# Adafruit_QT_Py.net
KiCad netlist of a schematic drawn in EAGLE
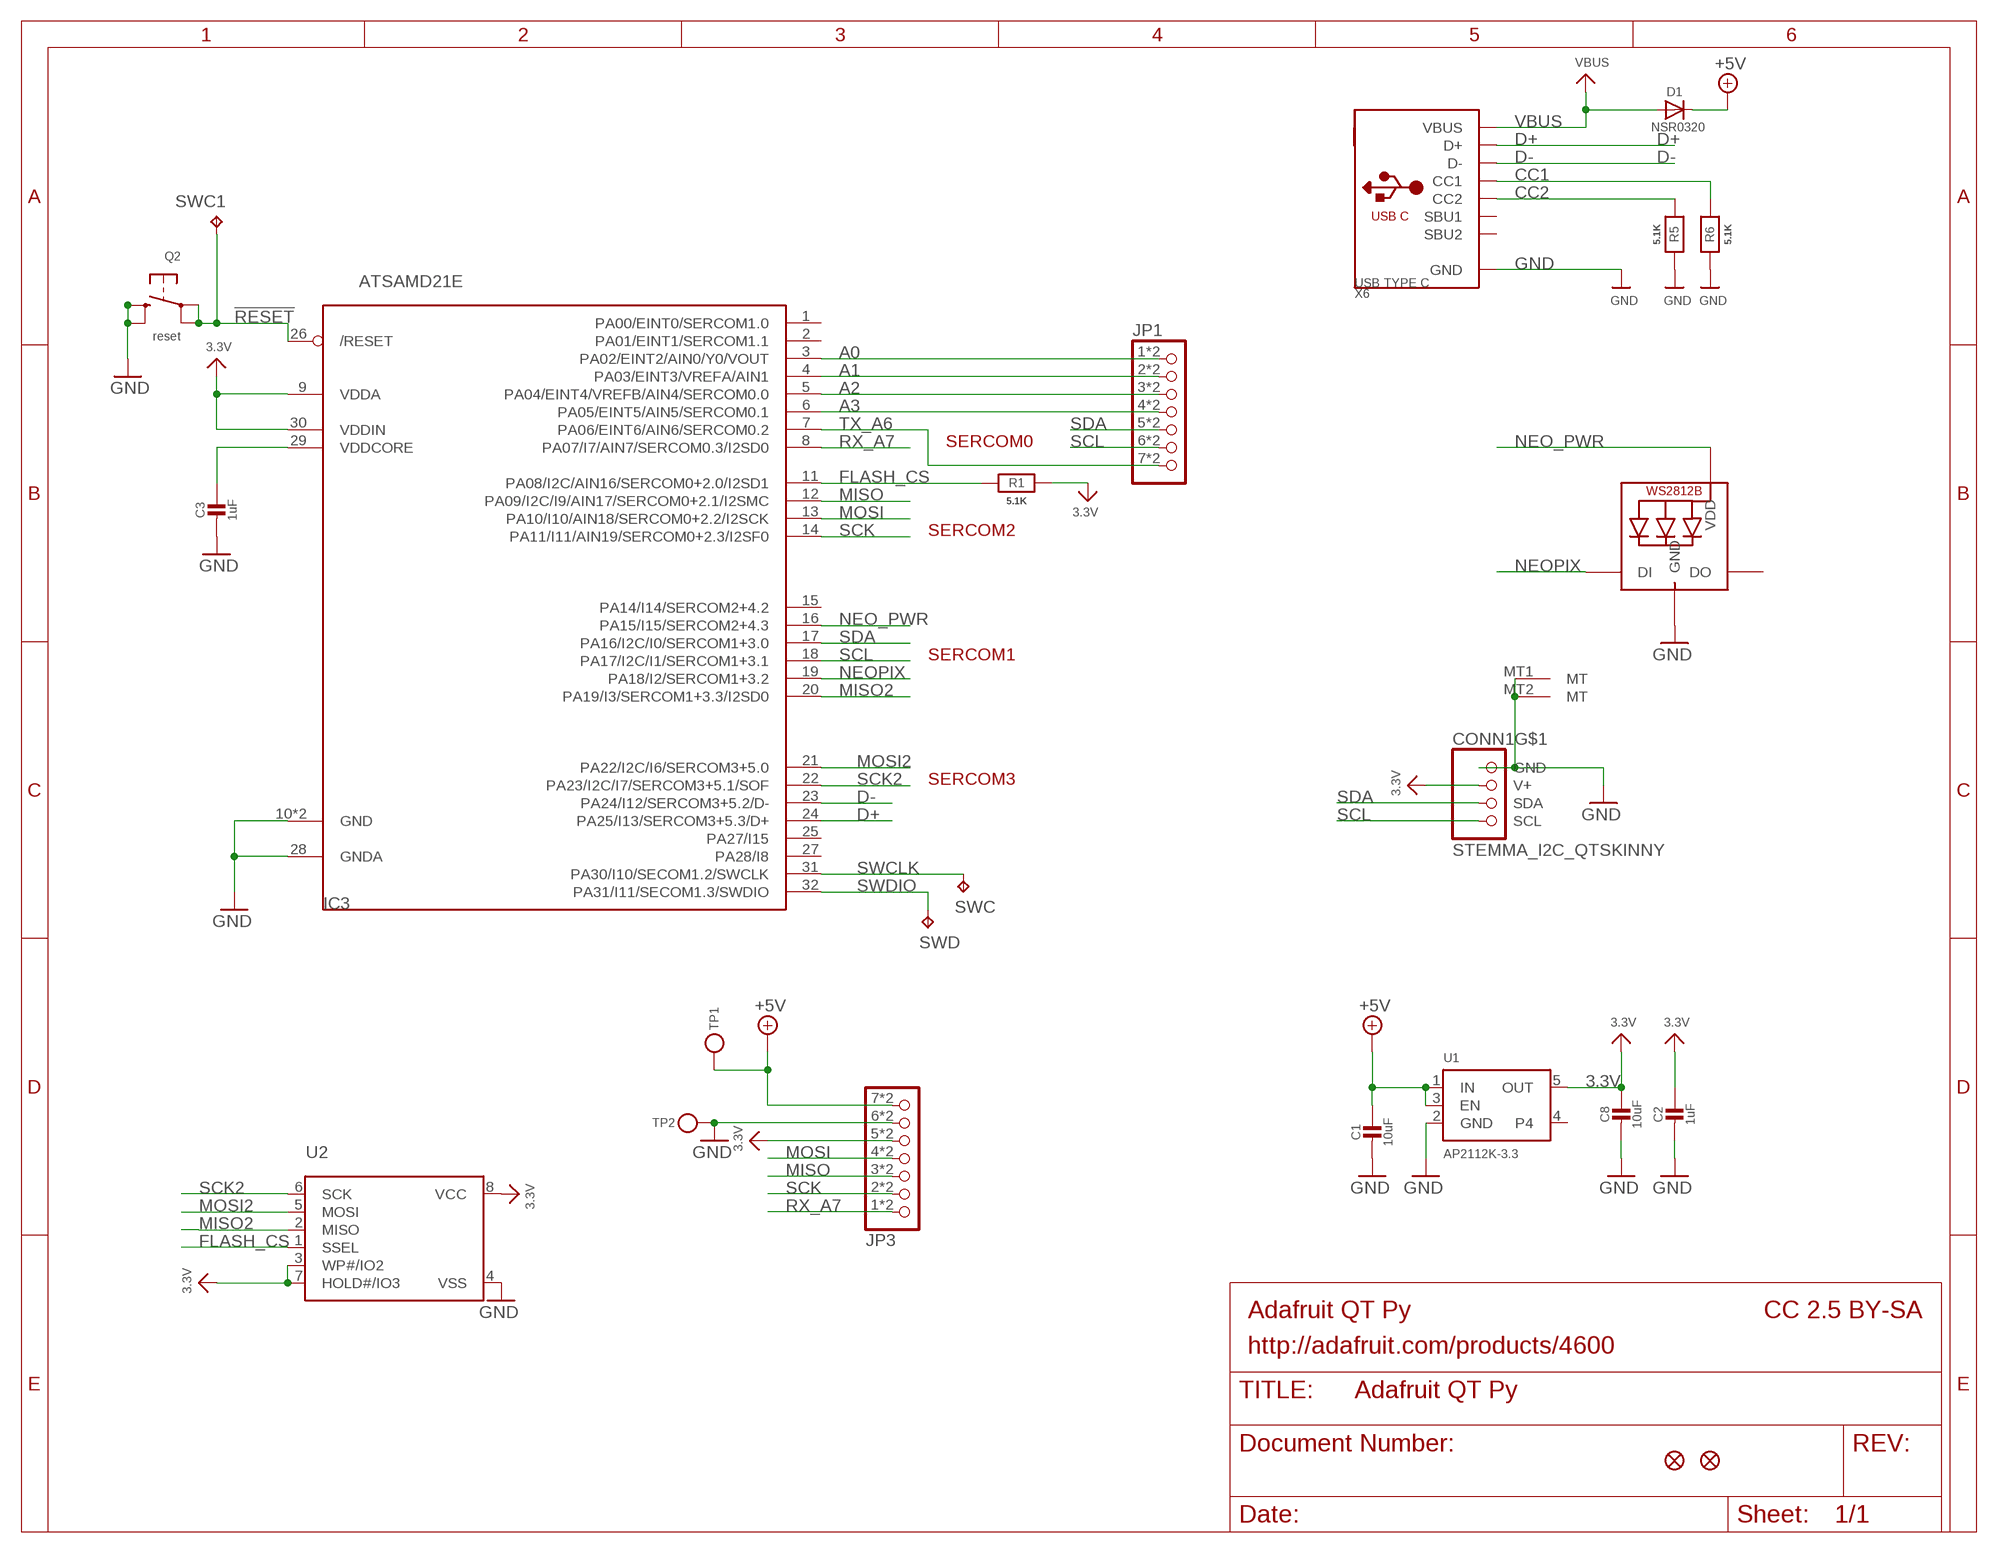
[diagram p0: schematic, sheet 1]

(export (version "E")
  (design (tool "Eeschema 10.0.6"))
  (components
    (comp (ref "C1")
      (value "10uF")
      (footprint "eagle-import:_0805MP")
      (libsource (lib "eagle-import") (part "CAP_CERAMIC_0805MP"))
    )
    (comp (ref "C2")
      (value "1uF")
      (footprint "eagle-import:_0402NO")
      (libsource (lib "eagle-import") (part "CAP_CERAMIC_0402NO"))
    )
    (comp (ref "C3")
      (value "1uF")
      (footprint "eagle-import:_0402NO")
      (libsource (lib "eagle-import") (part "CAP_CERAMIC_0402NO"))
    )
    (comp (ref "C8")
      (value "10uF")
      (footprint "eagle-import:_0805MP")
      (libsource (lib "eagle-import") (part "CAP_CERAMIC_0805MP"))
    )
    (comp (ref "CONN1")
      (value "STEMMA_I2C_QTSKINNY")
      (footprint "eagle-import:JST_SH4_SKINNY")
      (libsource (lib "eagle-import") (part "STEMMA_I2C_QTSKINNY"))
    )
    (comp (ref "D1")
      (value "NSR0320")
      (footprint "eagle-import:SOD-323_MINI")
      (libsource (lib "eagle-import") (part "DIODE_SOD323MINI"))
    )
    (comp (ref "IC3")
      (value "ATSAMD21E")
      (footprint "eagle-import:QFN32_5MM")
      (libsource (lib "eagle-import") (part "ATSAMD21E"))
    )
    (comp (ref "JP1")
      (value "HEADER-1X7_CASTEL")
      (footprint "eagle-import:1X07_CASTEL")
      (libsource (lib "eagle-import") (part "HEADER-1X7_CASTEL"))
    )
    (comp (ref "JP3")
      (value "HEADER-1X7_CASTEL")
      (footprint "eagle-import:1X07_CASTEL")
      (libsource (lib "eagle-import") (part "HEADER-1X7_CASTEL"))
    )
    (comp (ref "LED1")
      (value "WS2812B_SK6805_1515")
      (footprint "eagle-import:SK6805_1515")
      (libsource (lib "eagle-import") (part "WS2812B_SK6805_1515"))
    )
    (comp (ref "Q2")
      (value "reset")
      (footprint "eagle-import:BTN_KMR2_4.6X2.8")
      (libsource (lib "eagle-import") (part "SWITCH_TACT_SMT4.6X2.8"))
    )
    (comp (ref "R1")
      (value "5.1K")
      (footprint "eagle-import:_0402NO")
      (libsource (lib "eagle-import") (part "RESISTOR_0402NO"))
    )
    (comp (ref "R5")
      (value "5.1K")
      (footprint "eagle-import:_0402NO")
      (libsource (lib "eagle-import") (part "RESISTOR_0402NO"))
    )
    (comp (ref "R6")
      (value "5.1K")
      (footprint "eagle-import:_0402NO")
      (libsource (lib "eagle-import") (part "RESISTOR_0402NO"))
    )
    (comp (ref "SWC")
      (value "TPB1,27")
      (footprint "eagle-import:B1,27")
      (libsource (lib "eagle-import") (part "TPB1,27"))
    )
    (comp (ref "SWC1")
      (value "TPB1,27")
      (footprint "eagle-import:B1,27")
      (libsource (lib "eagle-import") (part "TPB1,27"))
    )
    (comp (ref "SWD")
      (value "TPB1,27")
      (footprint "eagle-import:B1,27")
      (libsource (lib "eagle-import") (part "TPB1,27"))
    )
    (comp (ref "TP1")
      (value "TESTPOINT_1X3")
      (footprint "eagle-import:TESTPOINT_RECT_1X3MM")
      (libsource (lib "eagle-import") (part "TESTPOINT_1X3"))
    )
    (comp (ref "TP2")
      (value "TESTPOINT_1X3")
      (footprint "eagle-import:TESTPOINT_RECT_1X3MM")
      (libsource (lib "eagle-import") (part "TESTPOINT_1X3"))
    )
    (comp (ref "U$6")
      (value "FIDUCIAL_1MM")
      (footprint "eagle-import:FIDUCIAL_1MM")
      (libsource (lib "eagle-import") (part "FIDUCIAL_1MM"))
    )
    (comp (ref "U$8")
      (value "FIDUCIAL_1MM")
      (footprint "eagle-import:FIDUCIAL_1MM")
      (libsource (lib "eagle-import") (part "FIDUCIAL_1MM"))
    )
    (comp (ref "U1")
      (value "AP2112K-3.3")
      (footprint "eagle-import:SOT23-5")
      (libsource (lib "eagle-import") (part "VREG_SOT23-5"))
    )
    (comp (ref "U2")
      (value "SPIFLASH_8PIN")
      (footprint "eagle-import:SOIC8_150MIL")
      (libsource (lib "eagle-import") (part "SPIFLASH_8PIN"))
    )
    (comp (ref "X6")
      (value "USB TYPE C")
      (footprint "eagle-import:USB_C_CUSB31-CFM2AX-01-X")
      (libsource (lib "eagle-import") (part "USB_C"))
    )
  )
  (nets
    (net (code "1") (name "+5V") (class "Default")
      (node (ref "C1") (pin "1") (pinfunction "1_1") (pintype "passive"))
      (node (ref "D1") (pin "C") (pinfunction "C_C") (pintype "passive"))
      (node (ref "JP3") (pin "7") (pinfunction "7_7") (pintype "passive"))
      (node (ref "JP3") (pin "7C") (pinfunction "7_7C") (pintype "passive"))
      (node (ref "TP1") (pin "P$1") (pinfunction "P$1_P$1") (pintype "bidirectional"))
      (node (ref "U1") (pin "1") (pinfunction "IN_1") (pintype "power_in"))
      (node (ref "U1") (pin "3") (pinfunction "EN_3") (pintype "input"))
    )
    (net (code "2") (name "/A0") (class "Default")
      (node (ref "IC3") (pin "3") (pinfunction "PA02/EINT2/AIN0/Y0/VOUT_3") (pintype "bidirectional"))
      (node (ref "JP1") (pin "1") (pinfunction "1_1") (pintype "passive"))
      (node (ref "JP1") (pin "1C") (pinfunction "1_1C") (pintype "passive"))
    )
    (net (code "3") (name "/A1") (class "Default")
      (node (ref "IC3") (pin "4") (pinfunction "PA03/EINT3/VREFA/AIN1_4") (pintype "bidirectional"))
      (node (ref "JP1") (pin "2") (pinfunction "2_2") (pintype "passive"))
      (node (ref "JP1") (pin "2C") (pinfunction "2_2C") (pintype "passive"))
    )
    (net (code "4") (name "/A2") (class "Default")
      (node (ref "IC3") (pin "5") (pinfunction "PA04/EINT4/VREFB/AIN4/SERCOM0.0_5") (pintype "bidirectional"))
      (node (ref "JP1") (pin "3") (pinfunction "3_3") (pintype "passive"))
      (node (ref "JP1") (pin "3C") (pinfunction "3_3C") (pintype "passive"))
    )
    (net (code "5") (name "/A3") (class "Default")
      (node (ref "IC3") (pin "6") (pinfunction "PA05/EINT5/AIN5/SERCOM0.1_6") (pintype "bidirectional"))
      (node (ref "JP1") (pin "4") (pinfunction "4_4") (pintype "passive"))
      (node (ref "JP1") (pin "4C") (pinfunction "4_4C") (pintype "passive"))
    )
    (net (code "6") (name "/CC1") (class "Default")
      (node (ref "R6") (pin "2") (pinfunction "2_2") (pintype "passive"))
      (node (ref "X6") (pin "A5") (pinfunction "CC1_A5") (pintype "bidirectional"))
    )
    (net (code "7") (name "/CC2") (class "Default")
      (node (ref "R5") (pin "2") (pinfunction "2_2") (pintype "passive"))
      (node (ref "X6") (pin "B5") (pinfunction "CC2_B5") (pintype "bidirectional"))
    )
    (net (code "8") (name "/D+") (class "Default")
      (node (ref "IC3") (pin "24") (pinfunction "PA25/I13/SERCOM3+5.3/D+_24") (pintype "bidirectional"))
      (node (ref "X6") (pin "A6") (pinfunction "D+_A6") (pintype "bidirectional"))
      (node (ref "X6") (pin "B6") (pinfunction "D+_B6") (pintype "bidirectional"))
    )
    (net (code "9") (name "/D-") (class "Default")
      (node (ref "IC3") (pin "23") (pinfunction "PA24/I12/SERCOM3+5.2/D-_23") (pintype "bidirectional"))
      (node (ref "X6") (pin "A7") (pinfunction "D-_A7") (pintype "bidirectional"))
      (node (ref "X6") (pin "B7") (pinfunction "D-_B7") (pintype "bidirectional"))
    )
    (net (code "10") (name "/FLASH_CS") (class "Default")
      (node (ref "IC3") (pin "11") (pinfunction "PA08/I2C/AIN16/SERCOM0+2.0/I2SD1_11") (pintype "bidirectional"))
      (node (ref "R1") (pin "2") (pinfunction "2_2") (pintype "passive"))
      (node (ref "U2") (pin "1") (pinfunction "SSEL_1") (pintype "bidirectional"))
    )
    (net (code "11") (name "/MISO") (class "Default")
      (node (ref "IC3") (pin "12") (pinfunction "PA09/I2C/I9/AIN17/SERCOM0+2.1/I2SMC_12") (pintype "bidirectional"))
      (node (ref "JP3") (pin "3") (pinfunction "3_3") (pintype "passive"))
      (node (ref "JP3") (pin "3C") (pinfunction "3_3C") (pintype "passive"))
    )
    (net (code "12") (name "/MISO2") (class "Default")
      (node (ref "IC3") (pin "20") (pinfunction "PA19/I3/SERCOM1+3.3/I2SD0_20") (pintype "bidirectional"))
      (node (ref "U2") (pin "2") (pinfunction "MISO_2") (pintype "bidirectional"))
    )
    (net (code "13") (name "/MOSI") (class "Default")
      (node (ref "IC3") (pin "13") (pinfunction "PA10/I10/AIN18/SERCOM0+2.2/I2SCK_13") (pintype "bidirectional"))
      (node (ref "JP3") (pin "4") (pinfunction "4_4") (pintype "passive"))
      (node (ref "JP3") (pin "4C") (pinfunction "4_4C") (pintype "passive"))
    )
    (net (code "14") (name "/MOSI2") (class "Default")
      (node (ref "IC3") (pin "21") (pinfunction "PA22/I2C/I6/SERCOM3+5.0_21") (pintype "bidirectional"))
      (node (ref "U2") (pin "5") (pinfunction "MOSI_5") (pintype "bidirectional"))
    )
    (net (code "15") (name "/NEOPIX") (class "Default")
      (node (ref "IC3") (pin "19") (pinfunction "PA18/I2/SERCOM1+3.2_19") (pintype "bidirectional"))
      (node (ref "LED1") (pin "1") (pinfunction "DI_1") (pintype "input"))
    )
    (net (code "16") (name "/NEO_PWR") (class "Default")
      (node (ref "IC3") (pin "16") (pinfunction "PA15/I15/SERCOM2+4.3_16") (pintype "bidirectional"))
      (node (ref "LED1") (pin "2") (pinfunction "VDD_2") (pintype "power_in"))
    )
    (net (code "17") (name "/RX_A7") (class "Default")
      (node (ref "IC3") (pin "8") (pinfunction "PA07/I7/AIN7/SERCOM0.3/I2SD0_8") (pintype "bidirectional"))
      (node (ref "JP3") (pin "1") (pinfunction "1_1") (pintype "passive"))
      (node (ref "JP3") (pin "1C") (pinfunction "1_1C") (pintype "passive"))
    )
    (net (code "18") (name "/SCK") (class "Default")
      (node (ref "IC3") (pin "14") (pinfunction "PA11/I11/AIN19/SERCOM0+2.3/I2SF0_14") (pintype "bidirectional"))
      (node (ref "JP3") (pin "2") (pinfunction "2_2") (pintype "passive"))
      (node (ref "JP3") (pin "2C") (pinfunction "2_2C") (pintype "passive"))
    )
    (net (code "19") (name "/SCK2") (class "Default")
      (node (ref "IC3") (pin "22") (pinfunction "PA23/I2C/I7/SERCOM3+5.1/SOF_22") (pintype "bidirectional"))
      (node (ref "U2") (pin "6") (pinfunction "SCK_6") (pintype "bidirectional"))
    )
    (net (code "20") (name "/SCL") (class "Default")
      (node (ref "CONN1") (pin "4") (pinfunction "SCL_4") (pintype "passive"))
      (node (ref "IC3") (pin "18") (pinfunction "PA17/I2C/I1/SERCOM1+3.1_18") (pintype "bidirectional"))
      (node (ref "JP1") (pin "6") (pinfunction "6_6") (pintype "passive"))
      (node (ref "JP1") (pin "6C") (pinfunction "6_6C") (pintype "passive"))
    )
    (net (code "21") (name "/SDA") (class "Default")
      (node (ref "CONN1") (pin "3") (pinfunction "SDA_3") (pintype "passive"))
      (node (ref "IC3") (pin "17") (pinfunction "PA16/I2C/I0/SERCOM1+3.0_17") (pintype "bidirectional"))
      (node (ref "JP1") (pin "5") (pinfunction "5_5") (pintype "passive"))
      (node (ref "JP1") (pin "5C") (pinfunction "5_5C") (pintype "passive"))
    )
    (net (code "22") (name "/SWCLK") (class "Default")
      (node (ref "IC3") (pin "31") (pinfunction "PA30/I10/SECOM1.2/SWCLK_31") (pintype "bidirectional"))
      (node (ref "SWC") (pin "TP") (pinfunction "TP_TP") (pintype "input"))
    )
    (net (code "23") (name "/SWDIO") (class "Default")
      (node (ref "IC3") (pin "32") (pinfunction "PA31/I11/SECOM1.3/SWDIO_32") (pintype "bidirectional"))
      (node (ref "SWD") (pin "TP") (pinfunction "TP_TP") (pintype "input"))
    )
    (net (code "24") (name "/TX_A6") (class "Default")
      (node (ref "IC3") (pin "7") (pinfunction "PA06/EINT6/AIN6/SERCOM0.2_7") (pintype "bidirectional"))
      (node (ref "JP1") (pin "7") (pinfunction "7_7") (pintype "passive"))
      (node (ref "JP1") (pin "7C") (pinfunction "7_7C") (pintype "passive"))
    )
    (net (code "25") (name "/~{RESET}") (class "Default")
      (node (ref "IC3") (pin "26") (pinfunction "/RESET_26") (pintype "bidirectional"))
      (node (ref "Q2") (pin "A") (pinfunction "P_A") (pintype "passive"))
      (node (ref "Q2") (pin "A'") (pinfunction "P1_A'") (pintype "passive"))
      (node (ref "SWC1") (pin "TP") (pinfunction "TP_TP") (pintype "input"))
    )
    (net (code "26") (name "3.3V") (class "Default")
      (node (ref "C2") (pin "1") (pinfunction "1_1") (pintype "passive"))
      (node (ref "C8") (pin "1") (pinfunction "1_1") (pintype "passive"))
      (node (ref "CONN1") (pin "2") (pinfunction "V+_2") (pintype "passive"))
      (node (ref "IC3") (pin "30") (pinfunction "VDDIN_30") (pintype "power_in"))
      (node (ref "IC3") (pin "9") (pinfunction "VDDA_9") (pintype "power_in"))
      (node (ref "JP3") (pin "5") (pinfunction "5_5") (pintype "passive"))
      (node (ref "JP3") (pin "5C") (pinfunction "5_5C") (pintype "passive"))
      (node (ref "R1") (pin "1") (pinfunction "1_1") (pintype "passive"))
      (node (ref "U1") (pin "5") (pinfunction "OUT_5") (pintype "power_in"))
      (node (ref "U2") (pin "3") (pinfunction "WP#/IO2_3") (pintype "bidirectional"))
      (node (ref "U2") (pin "7") (pinfunction "HOLD#/IO3_7") (pintype "bidirectional"))
      (node (ref "U2") (pin "8") (pinfunction "VCC_8") (pintype "bidirectional"))
    )
    (net (code "27") (name "GND") (class "Default")
      (node (ref "C1") (pin "2") (pinfunction "2_2") (pintype "passive"))
      (node (ref "C2") (pin "2") (pinfunction "2_2") (pintype "passive"))
      (node (ref "C3") (pin "2") (pinfunction "2_2") (pintype "passive"))
      (node (ref "C8") (pin "2") (pinfunction "2_2") (pintype "passive"))
      (node (ref "CONN1") (pin "1") (pinfunction "GND_1") (pintype "passive"))
      (node (ref "CONN1") (pin "MT1") (pinfunction "MT_MT1") (pintype "bidirectional"))
      (node (ref "CONN1") (pin "MT2") (pinfunction "MT_MT2") (pintype "bidirectional"))
      (node (ref "IC3") (pin "10") (pinfunction "GND_10") (pintype "power_in"))
      (node (ref "IC3") (pin "28") (pinfunction "GNDA_28") (pintype "power_in"))
      (node (ref "IC3") (pin "33") (pinfunction "GND_33") (pintype "power_in"))
      (node (ref "JP3") (pin "6") (pinfunction "6_6") (pintype "passive"))
      (node (ref "JP3") (pin "6C") (pinfunction "6_6C") (pintype "passive"))
      (node (ref "LED1") (pin "4") (pinfunction "GND_4") (pintype "power_in"))
      (node (ref "Q2") (pin "B") (pinfunction "S_B") (pintype "passive"))
      (node (ref "Q2") (pin "B'") (pinfunction "S1_B'") (pintype "passive"))
      (node (ref "R5") (pin "1") (pinfunction "1_1") (pintype "passive"))
      (node (ref "R6") (pin "1") (pinfunction "1_1") (pintype "passive"))
      (node (ref "TP2") (pin "P$1") (pinfunction "P$1_P$1") (pintype "bidirectional"))
      (node (ref "U1") (pin "2") (pinfunction "GND_2") (pintype "power_in"))
      (node (ref "U2") (pin "4") (pinfunction "VSS_4") (pintype "bidirectional"))
      (node (ref "X6") (pin "A1B12") (pinfunction "GND_A1B12") (pintype "power_in"))
      (node (ref "X6") (pin "B1A12") (pinfunction "GND_B1A12") (pintype "power_in"))
    )
    (net (code "28") (name "Net-(IC3-VDDCORE)") (class "Default")
      (node (ref "C3") (pin "1") (pinfunction "1_1") (pintype "passive"))
      (node (ref "IC3") (pin "29") (pinfunction "VDDCORE_29") (pintype "power_in"))
    )
    (net (code "29") (name "VBUS") (class "Default")
      (node (ref "D1") (pin "A") (pinfunction "A_A") (pintype "passive"))
      (node (ref "X6") (pin "A4B9") (pinfunction "VBUS_A4B9") (pintype "power_in"))
      (node (ref "X6") (pin "B4A9") (pinfunction "VBUS_B4A9") (pintype "power_in"))
    )
    (net (code "30") (name "unconnected-(IC3-PA00{slash}EINT0{slash}SERCOM1.0-Pad1)") (class "Default")
      (node (ref "IC3") (pin "1") (pinfunction "PA00/EINT0/SERCOM1.0_1") (pintype "bidirectional"))
    )
    (net (code "31") (name "unconnected-(IC3-PA01{slash}EINT1{slash}SERCOM1.1-Pad2)") (class "Default")
      (node (ref "IC3") (pin "2") (pinfunction "PA01/EINT1/SERCOM1.1_2") (pintype "bidirectional"))
    )
    (net (code "32") (name "unconnected-(IC3-PA14{slash}I14{slash}SERCOM2+4.2-Pad15)") (class "Default")
      (node (ref "IC3") (pin "15") (pinfunction "PA14/I14/SERCOM2+4.2_15") (pintype "bidirectional"))
    )
    (net (code "33") (name "unconnected-(IC3-PA27{slash}I15-Pad25)") (class "Default")
      (node (ref "IC3") (pin "25") (pinfunction "PA27/I15_25") (pintype "bidirectional"))
    )
    (net (code "34") (name "unconnected-(IC3-PA28{slash}I8-Pad27)") (class "Default")
      (node (ref "IC3") (pin "27") (pinfunction "PA28/I8_27") (pintype "bidirectional"))
    )
    (net (code "35") (name "unconnected-(LED1-DO-Pad3)") (class "Default")
      (node (ref "LED1") (pin "3") (pinfunction "DO_3") (pintype "output"))
    )
    (net (code "36") (name "unconnected-(U1-P4-Pad4)") (class "Default")
      (node (ref "U1") (pin "4") (pinfunction "P4_4") (pintype "bidirectional"))
    )
    (net (code "37") (name "unconnected-(X6-SBU1-PadA8)") (class "Default")
      (node (ref "X6") (pin "A8") (pinfunction "SBU1_A8") (pintype "bidirectional"))
    )
    (net (code "38") (name "unconnected-(X6-SBU2-PadB8)") (class "Default")
      (node (ref "X6") (pin "B8") (pinfunction "SBU2_B8") (pintype "bidirectional"))
    )
  )
)
